# Timebase_shcematics.net
KiCad netlist of a schematic drawn in Altium Designer
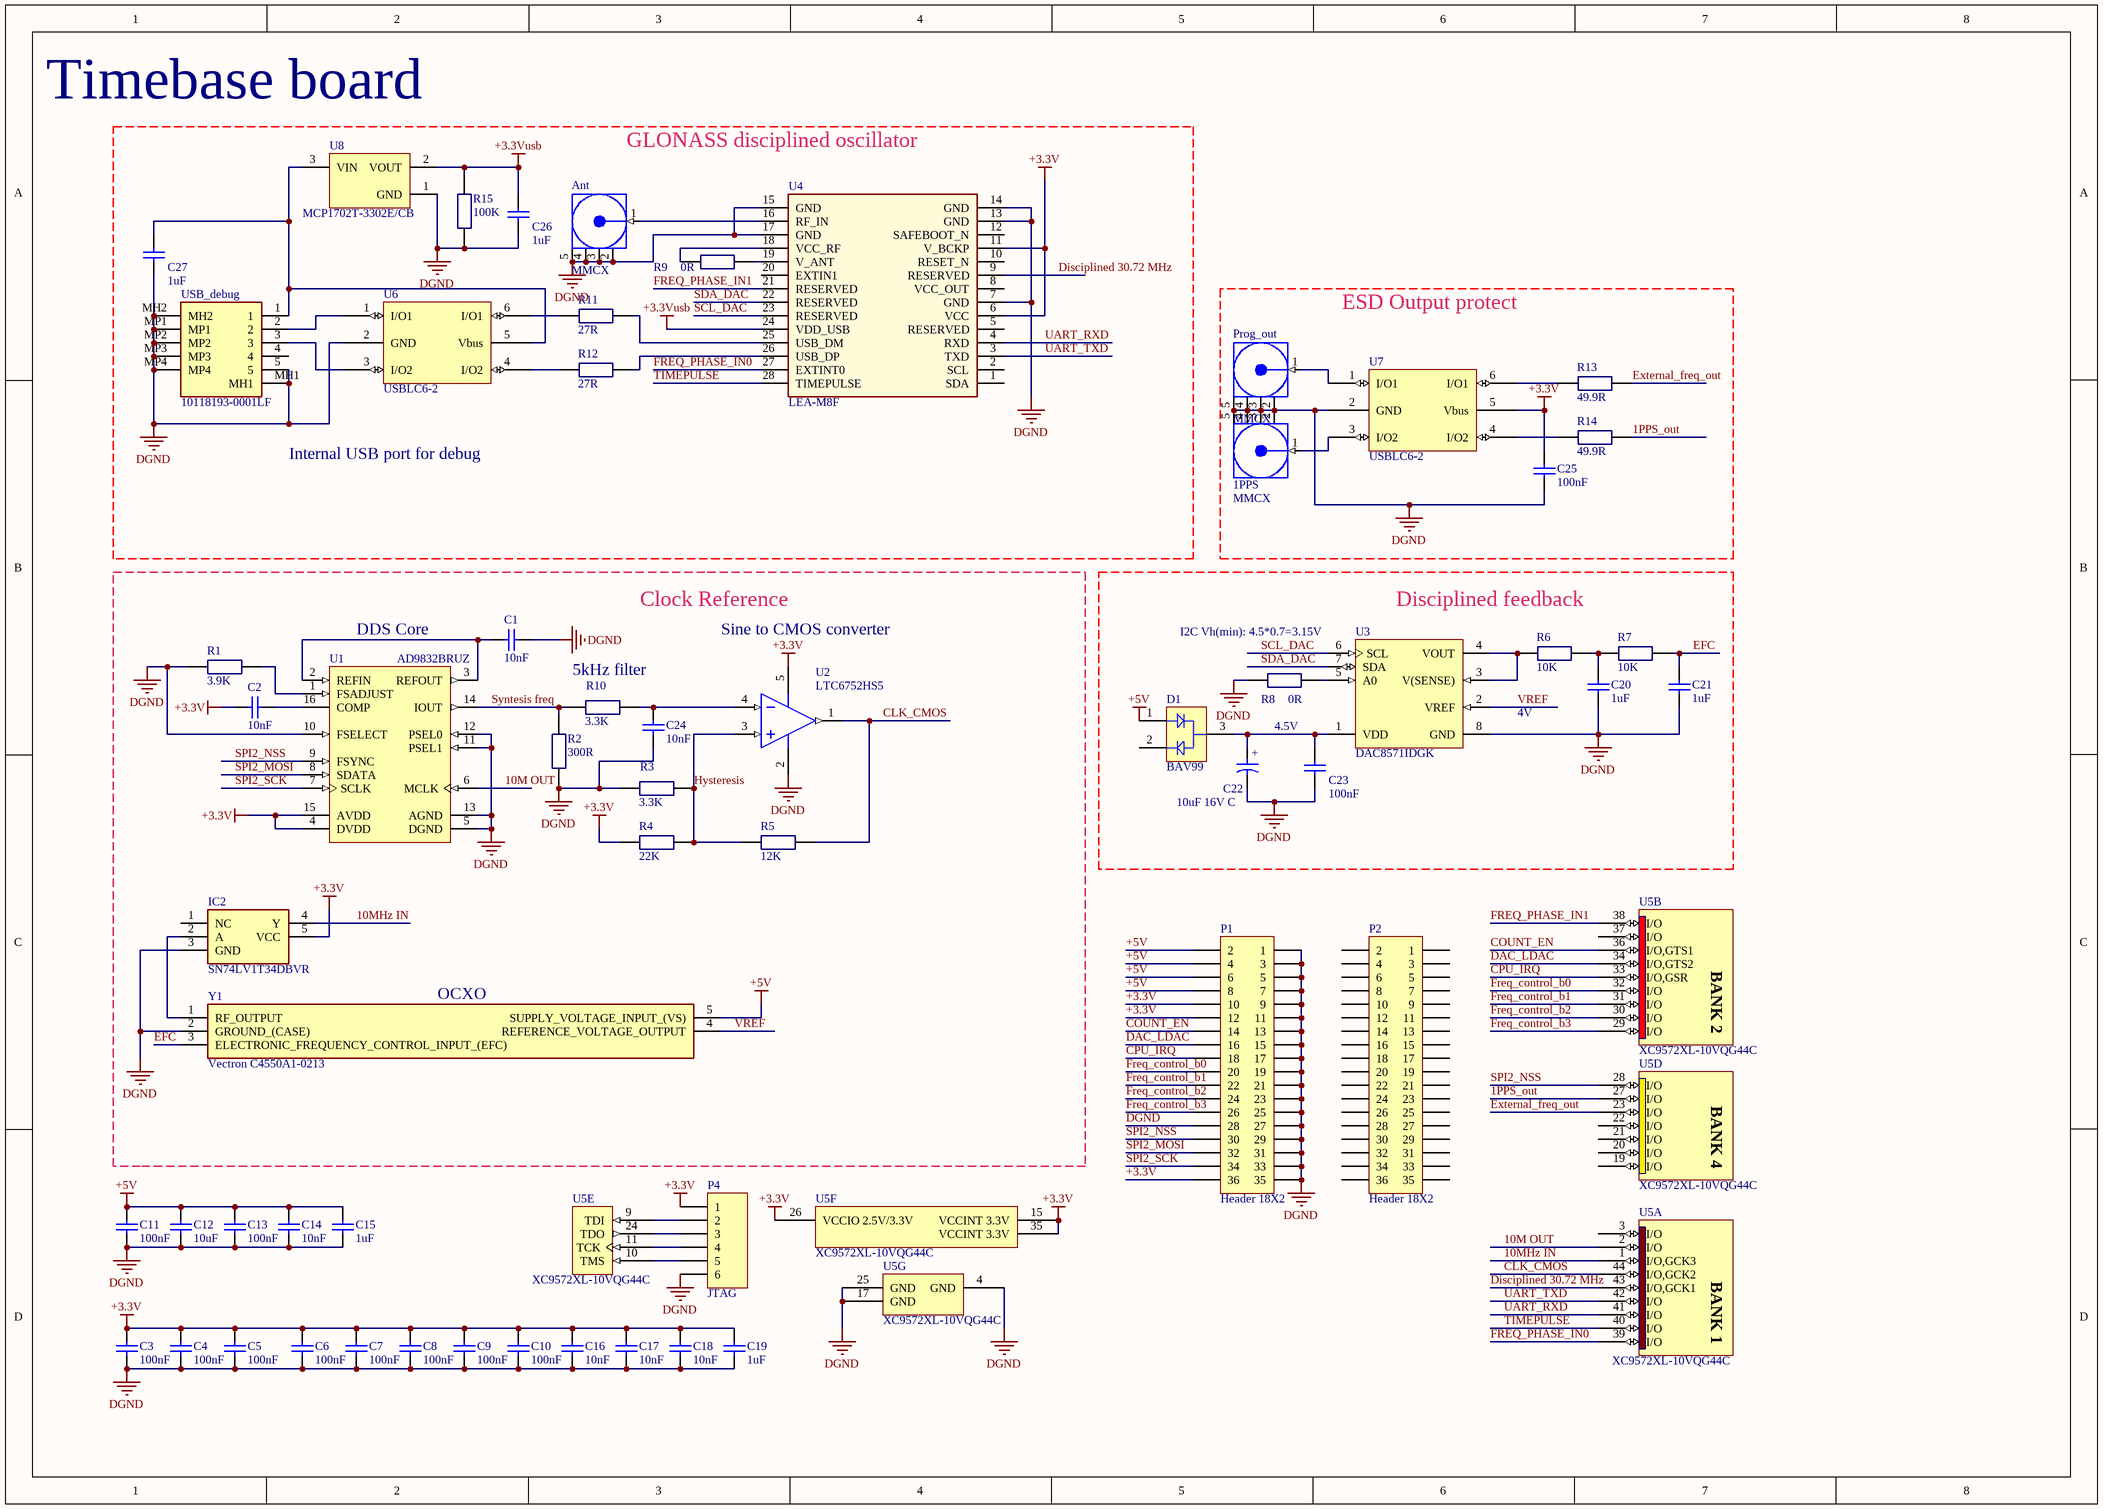
[diagram p0: Timebase_shcematics.SchDoc]

(export (version "E")
  (design (tool "Eeschema 10.0.6"))
  (components
    (comp (ref "1PPS")
      (value "MMCX")
      (footprint "MMCX2.54-V5")
      (description "RF Coaxial PCB Connector, MMCX; Thru-Hole, Vertical Mount Plug,  50 Ohm Impedance")
      (fields (field (name "PUBLISHER") "Altium Limited"))
      (libsource (lib "Miscellaneous Connectors") (part "COAX-M"))
    )
    (comp (ref "Ant")
      (value "MMCX")
      (footprint "MMCX2.54-V5")
      (description "RF Coaxial PCB Connector, MMCX; Thru-Hole, Vertical Mount Plug,  50 Ohm Impedance")
      (fields (field (name "PUBLISHER") "Altium Limited"))
      (libsource (lib "Miscellaneous Connectors") (part "COAX-M"))
    )
    (comp (ref "C1")
      (value "10nF")
      (footprint "CAP 0603")
      (description "Capacitor (Semiconductor SIM Model)")
      (fields (field (name "PUBLISHER") "Altium Limited"))
      (libsource (lib "Miscellaneous Devices") (part "Cap Semi"))
    )
    (comp (ref "C2")
      (value "10nF")
      (footprint "CAP 0603")
      (description "Capacitor (Semiconductor SIM Model)")
      (fields (field (name "PUBLISHER") "Altium Limited"))
      (libsource (lib "Miscellaneous Devices") (part "Cap Semi"))
    )
    (comp (ref "C3")
      (value "100nF")
      (footprint "CAP 0603")
      (description "Capacitor (Semiconductor SIM Model)")
      (fields (field (name "PUBLISHER") "Altium Limited"))
      (libsource (lib "Miscellaneous Devices") (part "Cap Semi"))
    )
    (comp (ref "C4")
      (value "100nF")
      (footprint "CAP 0603")
      (description "Capacitor (Semiconductor SIM Model)")
      (fields (field (name "PUBLISHER") "Altium Limited"))
      (libsource (lib "Miscellaneous Devices") (part "Cap Semi"))
    )
    (comp (ref "C5")
      (value "100nF")
      (footprint "CAP 0603")
      (description "Capacitor (Semiconductor SIM Model)")
      (fields (field (name "PUBLISHER") "Altium Limited"))
      (libsource (lib "Miscellaneous Devices") (part "Cap Semi"))
    )
    (comp (ref "C6")
      (value "100nF")
      (footprint "CAP 0603")
      (description "Capacitor (Semiconductor SIM Model)")
      (fields (field (name "PUBLISHER") "Altium Limited"))
      (libsource (lib "Miscellaneous Devices") (part "Cap Semi"))
    )
    (comp (ref "C7")
      (value "100nF")
      (footprint "CAP 0603")
      (description "Capacitor (Semiconductor SIM Model)")
      (fields (field (name "PUBLISHER") "Altium Limited"))
      (libsource (lib "Miscellaneous Devices") (part "Cap Semi"))
    )
    (comp (ref "C8")
      (value "100nF")
      (footprint "CAP 0603")
      (description "Capacitor (Semiconductor SIM Model)")
      (fields (field (name "PUBLISHER") "Altium Limited"))
      (libsource (lib "Miscellaneous Devices") (part "Cap Semi"))
    )
    (comp (ref "C9")
      (value "100nF")
      (footprint "CAP 0603")
      (description "Capacitor (Semiconductor SIM Model)")
      (fields (field (name "PUBLISHER") "Altium Limited"))
      (libsource (lib "Miscellaneous Devices") (part "Cap Semi"))
    )
    (comp (ref "C10")
      (value "100nF")
      (footprint "CAP 0603")
      (description "Capacitor (Semiconductor SIM Model)")
      (fields (field (name "PUBLISHER") "Altium Limited"))
      (libsource (lib "Miscellaneous Devices") (part "Cap Semi"))
    )
    (comp (ref "C11")
      (value "100nF")
      (footprint "CAP 0603")
      (description "Capacitor (Semiconductor SIM Model)")
      (fields (field (name "PUBLISHER") "Altium Limited"))
      (libsource (lib "Miscellaneous Devices") (part "Cap Semi"))
    )
    (comp (ref "C12")
      (value "10uF")
      (footprint "CAP 0603")
      (description "Capacitor (Semiconductor SIM Model)")
      (fields (field (name "PUBLISHER") "Altium Limited"))
      (libsource (lib "Miscellaneous Devices") (part "Cap Semi"))
    )
    (comp (ref "C13")
      (value "100nF")
      (footprint "CAP 0603")
      (description "Capacitor (Semiconductor SIM Model)")
      (fields (field (name "PUBLISHER") "Altium Limited"))
      (libsource (lib "Miscellaneous Devices") (part "Cap Semi"))
    )
    (comp (ref "C14")
      (value "10nF")
      (footprint "CAP 0603")
      (description "Capacitor (Semiconductor SIM Model)")
      (fields (field (name "PUBLISHER") "Altium Limited"))
      (libsource (lib "Miscellaneous Devices") (part "Cap Semi"))
    )
    (comp (ref "C15")
      (value "1uF")
      (footprint "CAP 0603")
      (description "Capacitor (Semiconductor SIM Model)")
      (fields (field (name "PUBLISHER") "Altium Limited"))
      (libsource (lib "Miscellaneous Devices") (part "Cap Semi"))
    )
    (comp (ref "C16")
      (value "10nF")
      (footprint "CAP 0603")
      (description "Capacitor (Semiconductor SIM Model)")
      (fields (field (name "PUBLISHER") "Altium Limited"))
      (libsource (lib "Miscellaneous Devices") (part "Cap Semi"))
    )
    (comp (ref "C17")
      (value "10nF")
      (footprint "CAP 0603")
      (description "Capacitor (Semiconductor SIM Model)")
      (fields (field (name "PUBLISHER") "Altium Limited"))
      (libsource (lib "Miscellaneous Devices") (part "Cap Semi"))
    )
    (comp (ref "C18")
      (value "10nF")
      (footprint "CAP 0603")
      (description "Capacitor (Semiconductor SIM Model)")
      (fields (field (name "PUBLISHER") "Altium Limited"))
      (libsource (lib "Miscellaneous Devices") (part "Cap Semi"))
    )
    (comp (ref "C19")
      (value "1uF")
      (footprint "CAP 0603")
      (description "Capacitor (Semiconductor SIM Model)")
      (fields (field (name "PUBLISHER") "Altium Limited"))
      (libsource (lib "Miscellaneous Devices") (part "Cap Semi"))
    )
    (comp (ref "C20")
      (value "1uF")
      (footprint "CAP 0603")
      (description "Capacitor (Semiconductor SIM Model)")
      (fields (field (name "PUBLISHER") "Altium Limited"))
      (libsource (lib "Miscellaneous Devices") (part "Cap Semi"))
    )
    (comp (ref "C21")
      (value "1uF")
      (footprint "CAP 0603")
      (description "Capacitor (Semiconductor SIM Model)")
      (fields (field (name "PUBLISHER") "Altium Limited"))
      (libsource (lib "Miscellaneous Devices") (part "Cap Semi"))
    )
    (comp (ref "C22")
      (value "10uF 16V C")
      (footprint "CAPMP6032X280N")
      (description "Polarised capacitor")
      (fields
        (field (name "PART NUMBER") "CTE6032-28_10UF_25V_10%_LESR0500")
        (field (name "VOLTAGE") "25V")
        (field (name "AUTHOR") "CERN DEM JLC")
      )
      (libsource (lib "Capacitors") (part "Capacitor - polarized"))
    )
    (comp (ref "C23")
      (value "100nF")
      (footprint "CAP 0603")
      (description "Capacitor (Semiconductor SIM Model)")
      (fields (field (name "PUBLISHER") "Altium Limited"))
      (libsource (lib "Miscellaneous Devices") (part "Cap Semi"))
    )
    (comp (ref "C24")
      (value "10nF")
      (footprint "CAP 0603")
      (description "Capacitor (Semiconductor SIM Model)")
      (fields (field (name "PUBLISHER") "Altium Limited"))
      (libsource (lib "Miscellaneous Devices") (part "Cap Semi"))
    )
    (comp (ref "C25")
      (value "100nF")
      (footprint "CAP 0603")
      (description "Capacitor (Semiconductor SIM Model)")
      (fields (field (name "PUBLISHER") "Altium Limited"))
      (libsource (lib "Miscellaneous Devices") (part "Cap Semi"))
    )
    (comp (ref "C26")
      (value "1uF")
      (footprint "CAP 0603")
      (description "Capacitor (Semiconductor SIM Model)")
      (fields (field (name "PUBLISHER") "Altium Limited"))
      (libsource (lib "Miscellaneous Devices") (part "Cap Semi"))
    )
    (comp (ref "C27")
      (value "1uF")
      (footprint "CAP 0603")
      (description "Capacitor (Semiconductor SIM Model)")
      (fields (field (name "PUBLISHER") "Altium Limited"))
      (libsource (lib "Miscellaneous Devices") (part "Cap Semi"))
    )
    (comp (ref "D1")
      (value "BAV99")
      (footprint "INF-SOT23_N")
      (description "Silicon Switching Diode, SOT23, Reel, Green")
      (fields (field (name "MANUFACTURER") "Infineon"))
      (libsource (lib "Infineon_Transistor_&_Diode") (part "BAV99"))
    )
    (comp (ref "IC2")
      (value "SN74LV1T34DBVR")
      (footprint "SamacSys:SOT95P280X145-5N")
      (description "Integrated Circuit")
      (fields (field (name "MOUSER PART NUMBER") "595-SN74LV1T34DBVR"))
      (libsource (lib "*") (part "SN74LV1T34DBVR"))
    )
    (comp (ref "P1")
      (value "Header 18X2")
      (footprint "HDR2X18")
      (description "Header, 18-Pin, Dual row")
      (fields (field (name "PUBLISHER") "Altium Limited"))
      (libsource (lib "Miscellaneous Connectors") (part "Header 18X2"))
    )
    (comp (ref "P2")
      (value "Header 18X2")
      (footprint "HDR2X18")
      (description "Header, 18-Pin, Dual row")
      (fields (field (name "PUBLISHER") "Altium Limited"))
      (libsource (lib "Miscellaneous Connectors") (part "Header 18X2"))
    )
    (comp (ref "P4")
      (value "JTAG")
      (footprint "HDR1X6")
      (description "Header, 6-Pin")
      (fields (field (name "PUBLISHER") "Altium Limited"))
      (libsource (lib "Miscellaneous Connectors") (part "Header 6"))
    )
    (comp (ref "Prog_out")
      (value "MMCX")
      (footprint "MMCX2.54-V5")
      (description "RF Coaxial PCB Connector, MMCX; Thru-Hole, Vertical Mount Plug,  50 Ohm Impedance")
      (fields (field (name "PUBLISHER") "Altium Limited"))
      (libsource (lib "Miscellaneous Connectors") (part "COAX-M"))
    )
    (comp (ref "R1")
      (value "3.9K")
      (footprint "1608[0603]")
      (libsource (lib "Микрон-3") (part "Resistor 0805"))
    )
    (comp (ref "R2")
      (value "300R")
      (footprint "Yegeo 0603")
      (libsource (lib "Микрон-3") (part "Resistor 0805"))
    )
    (comp (ref "R3")
      (value "3.3K")
      (footprint "Yegeo 0603")
      (libsource (lib "Микрон-3") (part "Resistor 0805"))
    )
    (comp (ref "R4")
      (value "22K")
      (footprint "Yegeo 0603")
      (libsource (lib "Микрон-3") (part "Resistor 0805"))
    )
    (comp (ref "R5")
      (value "12K")
      (footprint "Yegeo 0603")
      (libsource (lib "Микрон-3") (part "Resistor 0805"))
    )
    (comp (ref "R6")
      (value "10K")
      (footprint "1608[0603]")
      (libsource (lib "Микрон-3") (part "Resistor 0805"))
    )
    (comp (ref "R7")
      (value "10K")
      (footprint "1608[0603]")
      (libsource (lib "Микрон-3") (part "Resistor 0805"))
    )
    (comp (ref "R8")
      (value "0R")
      (footprint "1608[0603]")
      (libsource (lib "Микрон-3") (part "Resistor 0805"))
    )
    (comp (ref "R9")
      (value "0R")
      (footprint "1608[0603]")
      (libsource (lib "Микрон-3") (part "Resistor 0805"))
    )
    (comp (ref "R10")
      (value "3.3K")
      (footprint "Yegeo 0603")
      (libsource (lib "Микрон-3") (part "Resistor 0805"))
    )
    (comp (ref "R11")
      (value "27R")
      (footprint "1608[0603]")
      (libsource (lib "Микрон-3") (part "Resistor 0805"))
    )
    (comp (ref "R12")
      (value "27R")
      (footprint "1608[0603]")
      (libsource (lib "Микрон-3") (part "Resistor 0805"))
    )
    (comp (ref "R13")
      (value "49.9R")
      (footprint "1608[0603]")
      (libsource (lib "Микрон-3") (part "Resistor 0805"))
    )
    (comp (ref "R14")
      (value "49.9R")
      (footprint "1608[0603]")
      (libsource (lib "Микрон-3") (part "Resistor 0805"))
    )
    (comp (ref "R15")
      (value "100K")
      (footprint "1608[0603]")
      (libsource (lib "Микрон-3") (part "Resistor 0805"))
    )
    (comp (ref "U1")
      (value "AD9832BRUZ")
      (footprint "ADI-RU-16_N")
      (description "25 MHz Direct Digital Synthesizer, Waveform Generator, 10-Bit, Serial, RU-16, 96 Tube, Pb-Free")
      (libsource (lib "Ramp-generator") (part "AD9832BRUZ"))
    )
    (comp (ref "U2")
      (value "LTC6752HS5")
      (footprint "TI-DBV5_N")
      (fields (field (name "MANUFACTURER") "Texas Instruments") (field (name "PARTNUMBER") "OPA353NA/250"))
      (libsource (lib "TI Amplifiers and Linear Operational Amplifier Precision Amplifier Part One") (part "OPA353NA/250"))
    )
    (comp (ref "U3")
      (value "DAC8571IDGK")
      (footprint "TI-DGK8_N")
      (fields (field (name "MANUFACTURER") "Texas Instruments"))
      (libsource (lib "TI Data Converters Digital to Analog Converter") (part "DAC8571IDGK"))
    )
    (comp (ref "U4")
      (value "LEA-M8F")
      (footprint "LEA")
      (description "u-blox LEA GNSS module")
      (fields (field (name "MANUFACTURER") "u-blox"))
      (libsource (lib "ubloxLib") (part "LEA"))
    )
    (comp (ref "U5")
      (value "XC9572XL-10VQG44C")
      (footprint "VQG44_N")
      (fields (field (name "PUBLISHER") "Altium Limited"))
      (libsource (lib "") (part "XC9572XL-10VQG44C_1"))
    )
    (comp (ref "U6") (value "USBLC6-2") (footprint "SOT23-6L") (libsource (lib "Микрон-3") (part "USBLC6-2")))
    (comp (ref "U7") (value "USBLC6-2") (footprint "SOT23-6L") (libsource (lib "Микрон-3") (part "USBLC6-2")))
    (comp (ref "U8")
      (value "MCP1702T-3302E/CB")
      (footprint "SOT-23A-CB3_N")
      (description "250 mA Low Quiescent Current LDO Regulator, 3-Pin SOT-23A, Extended Temperature, Tape and Reel")
      (fields (field (name "PUBLISHER") "Altium Limited"))
      (libsource (lib "Microchip Power Mgt Line Regulator") (part "MCP1702T-3302E/CB"))
    )
    (comp (ref "USB_debug")
      (value "10118193-0001LF")
      (footprint "SamacSys:101181930001LF")
      (description "Connector")
      (fields (field (name "MOUSER PART NUMBER") "649-10118193-0001LF"))
      (libsource (lib "*") (part "10118193-0001LF"))
    )
    (comp (ref "Y1")
      (value "Vectron C4550A1-0213")
      (footprint "SamacSys:C4550C508SV120RFSA11128MHZ")
      (description "Crystal or Oscillator")
      (libsource (lib "SamacSys") (part "C4550C508SV120RFSA1112.8MHZ"))
    )
  )
  (nets
    (net (code "1") (name "+3.3V") (class "Default")
      (node (ref "C10") (pin "2") (pinfunction "2_2") (pintype "passive"))
      (node (ref "C16") (pin "2") (pinfunction "2_2") (pintype "passive"))
      (node (ref "C17") (pin "2") (pinfunction "2_2") (pintype "passive"))
      (node (ref "C18") (pin "2") (pinfunction "2_2") (pintype "passive"))
      (node (ref "C19") (pin "2") (pinfunction "2_2") (pintype "passive"))
      (node (ref "C2") (pin "1") (pinfunction "1_1") (pintype "passive"))
      (node (ref "C25") (pin "2") (pinfunction "2_2") (pintype "passive"))
      (node (ref "C3") (pin "2") (pinfunction "2_2") (pintype "passive"))
      (node (ref "C4") (pin "2") (pinfunction "2_2") (pintype "passive"))
      (node (ref "C5") (pin "2") (pinfunction "2_2") (pintype "passive"))
      (node (ref "C6") (pin "2") (pinfunction "2_2") (pintype "passive"))
      (node (ref "C7") (pin "2") (pinfunction "2_2") (pintype "passive"))
      (node (ref "C8") (pin "2") (pinfunction "2_2") (pintype "passive"))
      (node (ref "C9") (pin "2") (pinfunction "2_2") (pintype "passive"))
      (node (ref "IC2") (pin "5") (pinfunction "VCC_5") (pintype "passive"))
      (node (ref "P1") (pin "10") (pinfunction "10_10") (pintype "passive"))
      (node (ref "P1") (pin "12") (pinfunction "12_12") (pintype "passive"))
      (node (ref "P1") (pin "36") (pinfunction "36_36") (pintype "passive"))
      (node (ref "P4") (pin "1") (pinfunction "1_1") (pintype "passive"))
      (node (ref "R4") (pin "2") (pinfunction "2_2") (pintype "passive"))
      (node (ref "U1") (pin "15") (pinfunction "AVDD_15") (pintype "power_in"))
      (node (ref "U1") (pin "4") (pinfunction "DVDD_4") (pintype "power_in"))
      (node (ref "U2") (pin "5") (pinfunction "V+_5") (pintype "power_in"))
      (node (ref "U4") (pin "11") (pinfunction "V_BCKP_11") (pintype "passive"))
      (node (ref "U4") (pin "6") (pinfunction "VCC_6") (pintype "passive"))
      (node (ref "U5") (pin "15") (pinfunction "VCCINT_3.3V_15") (pintype "power_in"))
      (node (ref "U5") (pin "26") (pinfunction "VCCIO_2.5V/3.3V_26") (pintype "power_in"))
      (node (ref "U5") (pin "35") (pinfunction "VCCINT_3.3V_35") (pintype "power_in"))
      (node (ref "U7") (pin "5") (pinfunction "Vbus_5") (pintype "power_in"))
    )
    (net (code "2") (name "+3.3Vusb") (class "Default")
      (node (ref "C26") (pin "2") (pinfunction "2_2") (pintype "passive"))
      (node (ref "R15") (pin "1") (pinfunction "A_1") (pintype "passive"))
      (node (ref "U4") (pin "24") (pinfunction "VDD_USB_24") (pintype "passive"))
      (node (ref "U8") (pin "2") (pinfunction "VOUT_2") (pintype "power_in"))
    )
    (net (code "3") (name "+5V") (class "Default")
      (node (ref "C11") (pin "2") (pinfunction "2_2") (pintype "passive"))
      (node (ref "C12") (pin "2") (pinfunction "2_2") (pintype "passive"))
      (node (ref "C13") (pin "2") (pinfunction "2_2") (pintype "passive"))
      (node (ref "C14") (pin "2") (pinfunction "2_2") (pintype "passive"))
      (node (ref "C15") (pin "2") (pinfunction "2_2") (pintype "passive"))
      (node (ref "D1") (pin "1") (pinfunction "A1_1") (pintype "passive"))
      (node (ref "P1") (pin "2") (pinfunction "2_2") (pintype "passive"))
      (node (ref "P1") (pin "4") (pinfunction "4_4") (pintype "passive"))
      (node (ref "P1") (pin "6") (pinfunction "6_6") (pintype "passive"))
      (node (ref "P1") (pin "8") (pinfunction "8_8") (pintype "passive"))
      (node (ref "Y1") (pin "5") (pinfunction "SUPPLY_VOLTAGE_INPUT_(VS)_5") (pintype "passive"))
    )
    (net (code "4") (name "/1PPS_out") (class "Default")
      (node (ref "R14") (pin "1") (pinfunction "A_1") (pintype "passive"))
      (node (ref "U5") (pin "27") (pinfunction "I/O_27") (pintype "bidirectional"))
    )
    (net (code "5") (name "/10M OUT") (class "Default")
      (node (ref "U1") (pin "6") (pinfunction "MCLK_6") (pintype "input"))
      (node (ref "U5") (pin "2") (pinfunction "I/O_2") (pintype "bidirectional"))
    )
    (net (code "6") (name "/10MHz IN") (class "Default")
      (node (ref "IC2") (pin "4") (pinfunction "Y_4") (pintype "passive"))
      (node (ref "U5") (pin "1") (pinfunction "I/O,GCK3_1") (pintype "bidirectional"))
    )
    (net (code "7") (name "/CLK_CMOS") (class "Default")
      (node (ref "R5") (pin "1") (pinfunction "A_1") (pintype "passive"))
      (node (ref "U2") (pin "1") (pinfunction "OUT_1") (pintype "output"))
      (node (ref "U5") (pin "44") (pinfunction "I/O,GCK2_44") (pintype "bidirectional"))
    )
    (net (code "8") (name "/COUNT_EN") (class "Default")
      (node (ref "P1") (pin "14") (pinfunction "14_14") (pintype "passive"))
      (node (ref "U5") (pin "36") (pinfunction "I/O,GTS1_36") (pintype "bidirectional"))
    )
    (net (code "9") (name "/CPU_IRQ") (class "Default")
      (node (ref "P1") (pin "18") (pinfunction "18_18") (pintype "passive"))
      (node (ref "U5") (pin "33") (pinfunction "I/O,GSR_33") (pintype "bidirectional"))
    )
    (net (code "10") (name "/DAC_LDAC") (class "Default")
      (node (ref "P1") (pin "16") (pinfunction "16_16") (pintype "passive"))
      (node (ref "U5") (pin "34") (pinfunction "I/O,GTS2_34") (pintype "bidirectional"))
    )
    (net (code "11") (name "/Disciplined 30.72 MHz") (class "Default")
      (node (ref "U4") (pin "9") (pinfunction "RESERVED_9") (pintype "passive"))
      (node (ref "U5") (pin "43") (pinfunction "I/O,GCK1_43") (pintype "bidirectional"))
    )
    (net (code "12") (name "/EFC") (class "Default")
      (node (ref "C21") (pin "2") (pinfunction "2_2") (pintype "passive"))
      (node (ref "R7") (pin "1") (pinfunction "A_1") (pintype "passive"))
      (node (ref "Y1") (pin "3") (pinfunction "ELECTRONIC_FREQUENCY_CONTROL_INPUT_(EFC)_3") (pintype "passive"))
    )
    (net (code "13") (name "/External_freq_out") (class "Default")
      (node (ref "R13") (pin "1") (pinfunction "A_1") (pintype "passive"))
      (node (ref "U5") (pin "23") (pinfunction "I/O_23") (pintype "bidirectional"))
    )
    (net (code "14") (name "/FREQ_PHASE_IN0") (class "Default")
      (node (ref "U4") (pin "27") (pinfunction "EXTINT0_27") (pintype "passive"))
      (node (ref "U5") (pin "39") (pinfunction "I/O_39") (pintype "bidirectional"))
    )
    (net (code "15") (name "/FREQ_PHASE_IN1") (class "Default")
      (node (ref "U4") (pin "21") (pinfunction "RESERVED_21") (pintype "passive"))
      (node (ref "U5") (pin "38") (pinfunction "I/O_38") (pintype "bidirectional"))
    )
    (net (code "16") (name "/Freq_control_b0") (class "Default")
      (node (ref "P1") (pin "20") (pinfunction "20_20") (pintype "passive"))
      (node (ref "U5") (pin "32") (pinfunction "I/O_32") (pintype "bidirectional"))
    )
    (net (code "17") (name "/Freq_control_b1") (class "Default")
      (node (ref "P1") (pin "22") (pinfunction "22_22") (pintype "passive"))
      (node (ref "U5") (pin "31") (pinfunction "I/O_31") (pintype "bidirectional"))
    )
    (net (code "18") (name "/Freq_control_b2") (class "Default")
      (node (ref "P1") (pin "24") (pinfunction "24_24") (pintype "passive"))
      (node (ref "U5") (pin "30") (pinfunction "I/O_30") (pintype "bidirectional"))
    )
    (net (code "19") (name "/Freq_control_b3") (class "Default")
      (node (ref "P1") (pin "26") (pinfunction "26_26") (pintype "passive"))
      (node (ref "U5") (pin "29") (pinfunction "I/O_29") (pintype "bidirectional"))
    )
    (net (code "20") (name "/Hysteresis") (class "Default")
      (node (ref "R3") (pin "1") (pinfunction "A_1") (pintype "passive"))
      (node (ref "R4") (pin "1") (pinfunction "A_1") (pintype "passive"))
      (node (ref "R5") (pin "2") (pinfunction "2_2") (pintype "passive"))
      (node (ref "U2") (pin "3") (pinfunction "IN+_3") (pintype "input"))
    )
    (net (code "21") (name "/SCL_DAC") (class "Default")
      (node (ref "U3") (pin "6") (pinfunction "SCL_6") (pintype "input"))
      (node (ref "U4") (pin "23") (pinfunction "RESERVED_23") (pintype "passive"))
    )
    (net (code "22") (name "/SDA_DAC") (class "Default")
      (node (ref "U3") (pin "7") (pinfunction "SDA_7") (pintype "bidirectional"))
      (node (ref "U4") (pin "22") (pinfunction "RESERVED_22") (pintype "passive"))
    )
    (net (code "23") (name "/SPI2_MOSI") (class "Default")
      (node (ref "P1") (pin "32") (pinfunction "32_32") (pintype "passive"))
      (node (ref "U1") (pin "8") (pinfunction "SDATA_8") (pintype "input"))
    )
    (net (code "24") (name "/SPI2_NSS") (class "Default")
      (node (ref "P1") (pin "30") (pinfunction "30_30") (pintype "passive"))
      (node (ref "U1") (pin "9") (pinfunction "FSYNC_9") (pintype "input"))
      (node (ref "U5") (pin "28") (pinfunction "I/O_28") (pintype "bidirectional"))
    )
    (net (code "25") (name "/SPI2_SCK") (class "Default")
      (node (ref "P1") (pin "34") (pinfunction "34_34") (pintype "passive"))
      (node (ref "U1") (pin "7") (pinfunction "SCLK_7") (pintype "input"))
    )
    (net (code "26") (name "/Syntesis freq") (class "Default")
      (node (ref "R10") (pin "2") (pinfunction "2_2") (pintype "passive"))
      (node (ref "R2") (pin "2") (pinfunction "2_2") (pintype "passive"))
      (node (ref "U1") (pin "14") (pinfunction "IOUT_14") (pintype "output"))
    )
    (net (code "27") (name "/TIMEPULSE") (class "Default")
      (node (ref "U4") (pin "28") (pinfunction "TIMEPULSE_28") (pintype "passive"))
      (node (ref "U5") (pin "40") (pinfunction "I/O_40") (pintype "bidirectional"))
    )
    (net (code "28") (name "/UART_RXD") (class "Default")
      (node (ref "U4") (pin "4") (pinfunction "RXD_4") (pintype "passive"))
      (node (ref "U5") (pin "41") (pinfunction "I/O_41") (pintype "bidirectional"))
    )
    (net (code "29") (name "/UART_TXD") (class "Default")
      (node (ref "U4") (pin "3") (pinfunction "TXD_3") (pintype "passive"))
      (node (ref "U5") (pin "42") (pinfunction "I/O_42") (pintype "bidirectional"))
    )
    (net (code "30") (name "/VREF") (class "Default")
      (node (ref "U3") (pin "2") (pinfunction "VREF_2") (pintype "input"))
      (node (ref "Y1") (pin "4") (pinfunction "REFERENCE_VOLTAGE_OUTPUT_4") (pintype "passive"))
    )
    (net (code "31") (name "DGND") (class "Default")
      (node (ref "1PPS") (pin "2") (pinfunction "GND_2") (pintype "power_in"))
      (node (ref "1PPS") (pin "3") (pinfunction "GND_3") (pintype "power_in"))
      (node (ref "1PPS") (pin "4") (pinfunction "GND_4") (pintype "power_in"))
      (node (ref "1PPS") (pin "5") (pinfunction "GND_5") (pintype "power_in"))
      (node (ref "Ant") (pin "2") (pinfunction "GND_2") (pintype "power_in"))
      (node (ref "Ant") (pin "3") (pinfunction "GND_3") (pintype "power_in"))
      (node (ref "Ant") (pin "4") (pinfunction "GND_4") (pintype "power_in"))
      (node (ref "Ant") (pin "5") (pinfunction "GND_5") (pintype "power_in"))
      (node (ref "C1") (pin "2") (pinfunction "2_2") (pintype "passive"))
      (node (ref "C10") (pin "1") (pinfunction "1_1") (pintype "passive"))
      (node (ref "C11") (pin "1") (pinfunction "1_1") (pintype "passive"))
      (node (ref "C12") (pin "1") (pinfunction "1_1") (pintype "passive"))
      (node (ref "C13") (pin "1") (pinfunction "1_1") (pintype "passive"))
      (node (ref "C14") (pin "1") (pinfunction "1_1") (pintype "passive"))
      (node (ref "C15") (pin "1") (pinfunction "1_1") (pintype "passive"))
      (node (ref "C16") (pin "1") (pinfunction "1_1") (pintype "passive"))
      (node (ref "C17") (pin "1") (pinfunction "1_1") (pintype "passive"))
      (node (ref "C18") (pin "1") (pinfunction "1_1") (pintype "passive"))
      (node (ref "C19") (pin "1") (pinfunction "1_1") (pintype "passive"))
      (node (ref "C20") (pin "1") (pinfunction "1_1") (pintype "passive"))
      (node (ref "C21") (pin "1") (pinfunction "1_1") (pintype "passive"))
      (node (ref "C22") (pin "2") (pinfunction "2_2") (pintype "passive"))
      (node (ref "C23") (pin "1") (pinfunction "1_1") (pintype "passive"))
      (node (ref "C24") (pin "1") (pinfunction "1_1") (pintype "passive"))
      (node (ref "C25") (pin "1") (pinfunction "1_1") (pintype "passive"))
      (node (ref "C26") (pin "1") (pinfunction "1_1") (pintype "passive"))
      (node (ref "C27") (pin "1") (pinfunction "1_1") (pintype "passive"))
      (node (ref "C3") (pin "1") (pinfunction "1_1") (pintype "passive"))
      (node (ref "C4") (pin "1") (pinfunction "1_1") (pintype "passive"))
      (node (ref "C5") (pin "1") (pinfunction "1_1") (pintype "passive"))
      (node (ref "C6") (pin "1") (pinfunction "1_1") (pintype "passive"))
      (node (ref "C7") (pin "1") (pinfunction "1_1") (pintype "passive"))
      (node (ref "C8") (pin "1") (pinfunction "1_1") (pintype "passive"))
      (node (ref "C9") (pin "1") (pinfunction "1_1") (pintype "passive"))
      (node (ref "IC2") (pin "3") (pinfunction "GND_3") (pintype "passive"))
      (node (ref "P1") (pin "1") (pinfunction "1_1") (pintype "passive"))
      (node (ref "P1") (pin "11") (pinfunction "11_11") (pintype "passive"))
      (node (ref "P1") (pin "13") (pinfunction "13_13") (pintype "passive"))
      (node (ref "P1") (pin "15") (pinfunction "15_15") (pintype "passive"))
      (node (ref "P1") (pin "17") (pinfunction "17_17") (pintype "passive"))
      (node (ref "P1") (pin "19") (pinfunction "19_19") (pintype "passive"))
      (node (ref "P1") (pin "21") (pinfunction "21_21") (pintype "passive"))
      (node (ref "P1") (pin "23") (pinfunction "23_23") (pintype "passive"))
      (node (ref "P1") (pin "25") (pinfunction "25_25") (pintype "passive"))
      (node (ref "P1") (pin "27") (pinfunction "27_27") (pintype "passive"))
      (node (ref "P1") (pin "28") (pinfunction "28_28") (pintype "passive"))
      (node (ref "P1") (pin "29") (pinfunction "29_29") (pintype "passive"))
      (node (ref "P1") (pin "3") (pinfunction "3_3") (pintype "passive"))
      (node (ref "P1") (pin "31") (pinfunction "31_31") (pintype "passive"))
      (node (ref "P1") (pin "33") (pinfunction "33_33") (pintype "passive"))
      (node (ref "P1") (pin "35") (pinfunction "35_35") (pintype "passive"))
      (node (ref "P1") (pin "5") (pinfunction "5_5") (pintype "passive"))
      (node (ref "P1") (pin "7") (pinfunction "7_7") (pintype "passive"))
      (node (ref "P1") (pin "9") (pinfunction "9_9") (pintype "passive"))
      (node (ref "P4") (pin "6") (pinfunction "6_6") (pintype "passive"))
      (node (ref "Prog_out") (pin "2") (pinfunction "GND_2") (pintype "power_in"))
      (node (ref "Prog_out") (pin "3") (pinfunction "GND_3") (pintype "power_in"))
      (node (ref "Prog_out") (pin "4") (pinfunction "GND_4") (pintype "power_in"))
      (node (ref "Prog_out") (pin "5") (pinfunction "GND_5") (pintype "power_in"))
      (node (ref "R1") (pin "2") (pinfunction "2_2") (pintype "passive"))
      (node (ref "R15") (pin "2") (pinfunction "2_2") (pintype "passive"))
      (node (ref "R2") (pin "1") (pinfunction "A_1") (pintype "passive"))
      (node (ref "R3") (pin "2") (pinfunction "2_2") (pintype "passive"))
      (node (ref "R8") (pin "2") (pinfunction "2_2") (pintype "passive"))
      (node (ref "U1") (pin "10") (pinfunction "FSELECT_10") (pintype "input"))
      (node (ref "U1") (pin "11") (pinfunction "PSEL1_11") (pintype "input"))
      (node (ref "U1") (pin "12") (pinfunction "PSEL0_12") (pintype "input"))
      (node (ref "U1") (pin "13") (pinfunction "AGND_13") (pintype "power_in"))
      (node (ref "U1") (pin "5") (pinfunction "DGND_5") (pintype "power_in"))
      (node (ref "U2") (pin "2") (pinfunction "V-_2") (pintype "power_in"))
      (node (ref "U3") (pin "8") (pinfunction "GND_8") (pintype "power_in"))
      (node (ref "U4") (pin "13") (pinfunction "GND_13") (pintype "passive"))
      (node (ref "U4") (pin "14") (pinfunction "GND_14") (pintype "passive"))
      (node (ref "U4") (pin "15") (pinfunction "GND_15") (pintype "passive"))
      (node (ref "U4") (pin "17") (pinfunction "GND_17") (pintype "passive"))
      (node (ref "U4") (pin "7") (pinfunction "GND_7") (pintype "passive"))
      (node (ref "U5") (pin "17") (pinfunction "GND_17") (pintype "power_in"))
      (node (ref "U5") (pin "25") (pinfunction "GND_25") (pintype "power_in"))
      (node (ref "U5") (pin "4") (pinfunction "GND_4") (pintype "power_in"))
      (node (ref "U6") (pin "2") (pinfunction "GND_2") (pintype "power_in"))
      (node (ref "U7") (pin "2") (pinfunction "GND_2") (pintype "power_in"))
      (node (ref "U8") (pin "1") (pinfunction "GND_1") (pintype "power_in"))
      (node (ref "USB_debug") (pin "5") (pinfunction "5_5") (pintype "passive"))
      (node (ref "USB_debug") (pin "MH1") (pinfunction "MH1_MH1") (pintype "passive"))
      (node (ref "USB_debug") (pin "MH2") (pinfunction "MH2_MH2") (pintype "passive"))
      (node (ref "USB_debug") (pin "MP1") (pinfunction "MP1_MP1") (pintype "passive"))
      (node (ref "USB_debug") (pin "MP2") (pinfunction "MP2_MP2") (pintype "passive"))
      (node (ref "USB_debug") (pin "MP3") (pinfunction "MP3_MP3") (pintype "passive"))
      (node (ref "USB_debug") (pin "MP4") (pinfunction "MP4_MP4") (pintype "passive"))
      (node (ref "Y1") (pin "2") (pinfunction "GROUND_(CASE)_2") (pintype "passive"))
    )
    (net (code "32") (name "Net-(1PPS-Signal)") (class "Default")
      (node (ref "1PPS") (pin "1") (pinfunction "Signal_1") (pintype "input"))
      (node (ref "U7") (pin "3") (pinfunction "I/O2_3") (pintype "bidirectional"))
    )
    (net (code "33") (name "Net-(Ant-Signal)") (class "Default")
      (node (ref "Ant") (pin "1") (pinfunction "Signal_1") (pintype "input"))
      (node (ref "U4") (pin "16") (pinfunction "RF_IN_16") (pintype "passive"))
    )
    (net (code "34") (name "Net-(D1-C)") (class "Default")
      (node (ref "C22") (pin "1") (pinfunction "1_1") (pintype "passive"))
      (node (ref "C23") (pin "2") (pinfunction "2_2") (pintype "passive"))
      (node (ref "D1") (pin "3") (pinfunction "C_3") (pintype "passive"))
      (node (ref "U3") (pin "1") (pinfunction "VDD_1") (pintype "power_in"))
    )
    (net (code "35") (name "Net-(IC2-A)") (class "Default")
      (node (ref "IC2") (pin "2") (pinfunction "A_2") (pintype "passive"))
      (node (ref "Y1") (pin "1") (pinfunction "RF_OUTPUT_1") (pintype "passive"))
    )
    (net (code "36") (name "Net-(Prog_out-Signal)") (class "Default")
      (node (ref "Prog_out") (pin "1") (pinfunction "Signal_1") (pintype "input"))
      (node (ref "U7") (pin "1") (pinfunction "I/O1_1") (pintype "bidirectional"))
    )
    (net (code "37") (name "Net-(R1-A)") (class "Default")
      (node (ref "R1") (pin "1") (pinfunction "A_1") (pintype "passive"))
      (node (ref "U1") (pin "1") (pinfunction "FSADJUST_1") (pintype "input"))
    )
    (net (code "38") (name "Net-(R6-A)") (class "Default")
      (node (ref "C20") (pin "2") (pinfunction "2_2") (pintype "passive"))
      (node (ref "R6") (pin "1") (pinfunction "A_1") (pintype "passive"))
      (node (ref "R7") (pin "2") (pinfunction "2_2") (pintype "passive"))
    )
    (net (code "39") (name "Net-(R8-A)") (class "Default")
      (node (ref "R8") (pin "1") (pinfunction "A_1") (pintype "passive"))
      (node (ref "U3") (pin "5") (pinfunction "A0_5") (pintype "input"))
    )
    (net (code "40") (name "Net-(R9-A)") (class "Default")
      (node (ref "R9") (pin "1") (pinfunction "A_1") (pintype "passive"))
      (node (ref "U4") (pin "19") (pinfunction "V_ANT_19") (pintype "passive"))
    )
    (net (code "41") (name "Net-(R10-A)") (class "Default")
      (node (ref "C24") (pin "2") (pinfunction "2_2") (pintype "passive"))
      (node (ref "R10") (pin "1") (pinfunction "A_1") (pintype "passive"))
      (node (ref "U2") (pin "4") (pinfunction "IN-_4") (pintype "input"))
    )
    (net (code "42") (name "Net-(R11-A)") (class "Default")
      (node (ref "R11") (pin "1") (pinfunction "A_1") (pintype "passive"))
      (node (ref "U4") (pin "25") (pinfunction "USB_DM_25") (pintype "passive"))
    )
    (net (code "43") (name "Net-(R11-Pad2)") (class "Default")
      (node (ref "R11") (pin "2") (pinfunction "2_2") (pintype "passive"))
      (node (ref "U6") (pin "6") (pinfunction "I/O1_6") (pintype "bidirectional"))
    )
    (net (code "44") (name "Net-(R12-A)") (class "Default")
      (node (ref "R12") (pin "1") (pinfunction "A_1") (pintype "passive"))
      (node (ref "U4") (pin "26") (pinfunction "USB_DP_26") (pintype "passive"))
    )
    (net (code "45") (name "Net-(R12-Pad2)") (class "Default")
      (node (ref "R12") (pin "2") (pinfunction "2_2") (pintype "passive"))
      (node (ref "U6") (pin "4") (pinfunction "I/O2_4") (pintype "bidirectional"))
    )
    (net (code "46") (name "Net-(R13-Pad2)") (class "Default")
      (node (ref "R13") (pin "2") (pinfunction "2_2") (pintype "passive"))
      (node (ref "U7") (pin "6") (pinfunction "I/O1_6") (pintype "bidirectional"))
    )
    (net (code "47") (name "Net-(R14-Pad2)") (class "Default")
      (node (ref "R14") (pin "2") (pinfunction "2_2") (pintype "passive"))
      (node (ref "U7") (pin "4") (pinfunction "I/O2_4") (pintype "bidirectional"))
    )
    (net (code "48") (name "Net-(U1-COMP)") (class "Default")
      (node (ref "C2") (pin "2") (pinfunction "2_2") (pintype "passive"))
      (node (ref "U1") (pin "16") (pinfunction "COMP_16") (pintype "passive"))
    )
    (net (code "49") (name "Net-(U1-REFIN)") (class "Default")
      (node (ref "C1") (pin "1") (pinfunction "1_1") (pintype "passive"))
      (node (ref "U1") (pin "2") (pinfunction "REFIN_2") (pintype "input"))
      (node (ref "U1") (pin "3") (pinfunction "REFOUT_3") (pintype "output"))
    )
    (net (code "50") (name "Net-(U3-V(SENSE))") (class "Default")
      (node (ref "R6") (pin "2") (pinfunction "2_2") (pintype "passive"))
      (node (ref "U3") (pin "3") (pinfunction "V(SENSE)_3") (pintype "input"))
      (node (ref "U3") (pin "4") (pinfunction "VOUT_4") (pintype "tri_state"))
    )
    (net (code "51") (name "Net-(U4-VCC_RF)") (class "Default")
      (node (ref "R9") (pin "2") (pinfunction "2_2") (pintype "passive"))
      (node (ref "U4") (pin "18") (pinfunction "VCC_RF_18") (pintype "passive"))
    )
    (net (code "52") (name "Net-(U5E-TCK)") (class "Default")
      (node (ref "P4") (pin "4") (pinfunction "4_4") (pintype "passive"))
      (node (ref "U5") (pin "11") (pinfunction "TCK_11") (pintype "input"))
    )
    (net (code "53") (name "Net-(U5E-TDI)") (class "Default")
      (node (ref "P4") (pin "2") (pinfunction "2_2") (pintype "passive"))
      (node (ref "U5") (pin "9") (pinfunction "TDI_9") (pintype "input"))
    )
    (net (code "54") (name "Net-(U5E-TDO)") (class "Default")
      (node (ref "P4") (pin "3") (pinfunction "3_3") (pintype "passive"))
      (node (ref "U5") (pin "24") (pinfunction "TDO_24") (pintype "output"))
    )
    (net (code "55") (name "Net-(U5E-TMS)") (class "Default")
      (node (ref "P4") (pin "5") (pinfunction "5_5") (pintype "passive"))
      (node (ref "U5") (pin "10") (pinfunction "TMS_10") (pintype "input"))
    )
    (net (code "56") (name "Net-(U6-I{slash}O1-Pad1)") (class "Default")
      (node (ref "U6") (pin "1") (pinfunction "I/O1_1") (pintype "bidirectional"))
      (node (ref "USB_debug") (pin "2") (pinfunction "2_2") (pintype "passive"))
    )
    (net (code "57") (name "Net-(U6-I{slash}O2-Pad3)") (class "Default")
      (node (ref "U6") (pin "3") (pinfunction "I/O2_3") (pintype "bidirectional"))
      (node (ref "USB_debug") (pin "3") (pinfunction "3_3") (pintype "passive"))
    )
    (net (code "58") (name "Net-(U6-Vbus)") (class "Default")
      (node (ref "C27") (pin "2") (pinfunction "2_2") (pintype "passive"))
      (node (ref "U6") (pin "5") (pinfunction "Vbus_5") (pintype "power_in"))
      (node (ref "U8") (pin "3") (pinfunction "VIN_3") (pintype "power_in"))
      (node (ref "USB_debug") (pin "1") (pinfunction "1_1") (pintype "passive"))
    )
    (net (code "59") (name "unconnected-(D1-K2-Pad2)") (class "Default")
      (node (ref "D1") (pin "2") (pinfunction "K2_2") (pintype "passive"))
    )
    (net (code "60") (name "unconnected-(IC2-NC-Pad1)") (class "Default")
      (node (ref "IC2") (pin "1") (pinfunction "NC_1") (pintype "passive"))
    )
    (net (code "61") (name "unconnected-(P2-Pad1)") (class "Default")
      (node (ref "P2") (pin "1") (pinfunction "1_1") (pintype "passive"))
    )
    (net (code "62") (name "unconnected-(P2-Pad2)") (class "Default")
      (node (ref "P2") (pin "2") (pinfunction "2_2") (pintype "passive"))
    )
    (net (code "63") (name "unconnected-(P2-Pad3)") (class "Default")
      (node (ref "P2") (pin "3") (pinfunction "3_3") (pintype "passive"))
    )
    (net (code "64") (name "unconnected-(P2-Pad4)") (class "Default")
      (node (ref "P2") (pin "4") (pinfunction "4_4") (pintype "passive"))
    )
    (net (code "65") (name "unconnected-(P2-Pad5)") (class "Default")
      (node (ref "P2") (pin "5") (pinfunction "5_5") (pintype "passive"))
    )
    (net (code "66") (name "unconnected-(P2-Pad6)") (class "Default")
      (node (ref "P2") (pin "6") (pinfunction "6_6") (pintype "passive"))
    )
    (net (code "67") (name "unconnected-(P2-Pad7)") (class "Default")
      (node (ref "P2") (pin "7") (pinfunction "7_7") (pintype "passive"))
    )
    (net (code "68") (name "unconnected-(P2-Pad8)") (class "Default")
      (node (ref "P2") (pin "8") (pinfunction "8_8") (pintype "passive"))
    )
    (net (code "69") (name "unconnected-(P2-Pad9)") (class "Default")
      (node (ref "P2") (pin "9") (pinfunction "9_9") (pintype "passive"))
    )
    (net (code "70") (name "unconnected-(P2-Pad10)") (class "Default")
      (node (ref "P2") (pin "10") (pinfunction "10_10") (pintype "passive"))
    )
    (net (code "71") (name "unconnected-(P2-Pad11)") (class "Default")
      (node (ref "P2") (pin "11") (pinfunction "11_11") (pintype "passive"))
    )
    (net (code "72") (name "unconnected-(P2-Pad12)") (class "Default")
      (node (ref "P2") (pin "12") (pinfunction "12_12") (pintype "passive"))
    )
    (net (code "73") (name "unconnected-(P2-Pad13)") (class "Default")
      (node (ref "P2") (pin "13") (pinfunction "13_13") (pintype "passive"))
    )
    (net (code "74") (name "unconnected-(P2-Pad14)") (class "Default")
      (node (ref "P2") (pin "14") (pinfunction "14_14") (pintype "passive"))
    )
    (net (code "75") (name "unconnected-(P2-Pad15)") (class "Default")
      (node (ref "P2") (pin "15") (pinfunction "15_15") (pintype "passive"))
    )
    (net (code "76") (name "unconnected-(P2-Pad16)") (class "Default")
      (node (ref "P2") (pin "16") (pinfunction "16_16") (pintype "passive"))
    )
    (net (code "77") (name "unconnected-(P2-Pad17)") (class "Default")
      (node (ref "P2") (pin "17") (pinfunction "17_17") (pintype "passive"))
    )
    (net (code "78") (name "unconnected-(P2-Pad18)") (class "Default")
      (node (ref "P2") (pin "18") (pinfunction "18_18") (pintype "passive"))
    )
    (net (code "79") (name "unconnected-(P2-Pad19)") (class "Default")
      (node (ref "P2") (pin "19") (pinfunction "19_19") (pintype "passive"))
    )
    (net (code "80") (name "unconnected-(P2-Pad20)") (class "Default")
      (node (ref "P2") (pin "20") (pinfunction "20_20") (pintype "passive"))
    )
    (net (code "81") (name "unconnected-(P2-Pad21)") (class "Default")
      (node (ref "P2") (pin "21") (pinfunction "21_21") (pintype "passive"))
    )
    (net (code "82") (name "unconnected-(P2-Pad22)") (class "Default")
      (node (ref "P2") (pin "22") (pinfunction "22_22") (pintype "passive"))
    )
    (net (code "83") (name "unconnected-(P2-Pad23)") (class "Default")
      (node (ref "P2") (pin "23") (pinfunction "23_23") (pintype "passive"))
    )
    (net (code "84") (name "unconnected-(P2-Pad24)") (class "Default")
      (node (ref "P2") (pin "24") (pinfunction "24_24") (pintype "passive"))
    )
    (net (code "85") (name "unconnected-(P2-Pad25)") (class "Default")
      (node (ref "P2") (pin "25") (pinfunction "25_25") (pintype "passive"))
    )
    (net (code "86") (name "unconnected-(P2-Pad26)") (class "Default")
      (node (ref "P2") (pin "26") (pinfunction "26_26") (pintype "passive"))
    )
    (net (code "87") (name "unconnected-(P2-Pad27)") (class "Default")
      (node (ref "P2") (pin "27") (pinfunction "27_27") (pintype "passive"))
    )
    (net (code "88") (name "unconnected-(P2-Pad28)") (class "Default")
      (node (ref "P2") (pin "28") (pinfunction "28_28") (pintype "passive"))
    )
    (net (code "89") (name "unconnected-(P2-Pad29)") (class "Default")
      (node (ref "P2") (pin "29") (pinfunction "29_29") (pintype "passive"))
    )
    (net (code "90") (name "unconnected-(P2-Pad30)") (class "Default")
      (node (ref "P2") (pin "30") (pinfunction "30_30") (pintype "passive"))
    )
    (net (code "91") (name "unconnected-(P2-Pad31)") (class "Default")
      (node (ref "P2") (pin "31") (pinfunction "31_31") (pintype "passive"))
    )
    (net (code "92") (name "unconnected-(P2-Pad32)") (class "Default")
      (node (ref "P2") (pin "32") (pinfunction "32_32") (pintype "passive"))
    )
    (net (code "93") (name "unconnected-(P2-Pad33)") (class "Default")
      (node (ref "P2") (pin "33") (pinfunction "33_33") (pintype "passive"))
    )
    (net (code "94") (name "unconnected-(P2-Pad34)") (class "Default")
      (node (ref "P2") (pin "34") (pinfunction "34_34") (pintype "passive"))
    )
    (net (code "95") (name "unconnected-(P2-Pad35)") (class "Default")
      (node (ref "P2") (pin "35") (pinfunction "35_35") (pintype "passive"))
    )
    (net (code "96") (name "unconnected-(P2-Pad36)") (class "Default")
      (node (ref "P2") (pin "36") (pinfunction "36_36") (pintype "passive"))
    )
    (net (code "97") (name "unconnected-(U4-EXTIN1-Pad20)") (class "Default")
      (node (ref "U4") (pin "20") (pinfunction "EXTIN1_20") (pintype "passive"))
    )
    (net (code "98") (name "unconnected-(U4-RESERVED-Pad5)") (class "Default")
      (node (ref "U4") (pin "5") (pinfunction "RESERVED_5") (pintype "passive"))
    )
    (net (code "99") (name "unconnected-(U4-RESET_N-Pad10)") (class "Default")
      (node (ref "U4") (pin "10") (pinfunction "RESET_N_10") (pintype "passive"))
    )
    (net (code "100") (name "unconnected-(U4-SAFEBOOT_N-Pad12)") (class "Default")
      (node (ref "U4") (pin "12") (pinfunction "SAFEBOOT_N_12") (pintype "passive"))
    )
    (net (code "101") (name "unconnected-(U4-SCL-Pad2)") (class "Default")
      (node (ref "U4") (pin "2") (pinfunction "SCL_2") (pintype "passive"))
    )
    (net (code "102") (name "unconnected-(U4-SDA-Pad1)") (class "Default")
      (node (ref "U4") (pin "1") (pinfunction "SDA_1") (pintype "passive"))
    )
    (net (code "103") (name "unconnected-(U4-VCC_OUT-Pad8)") (class "Default")
      (node (ref "U4") (pin "8") (pinfunction "VCC_OUT_8") (pintype "passive"))
    )
    (net (code "104") (name "unconnected-(U5A-I{slash}O-Pad3)") (class "Default")
      (node (ref "U5") (pin "3") (pinfunction "I/O_3") (pintype "bidirectional"))
    )
    (net (code "105") (name "unconnected-(U5B-I{slash}O-Pad37)") (class "Default")
      (node (ref "U5") (pin "37") (pinfunction "I/O_37") (pintype "bidirectional"))
    )
    (net (code "106") (name "unconnected-(U5D-I{slash}O-Pad19)") (class "Default")
      (node (ref "U5") (pin "19") (pinfunction "I/O_19") (pintype "bidirectional"))
    )
    (net (code "107") (name "unconnected-(U5D-I{slash}O-Pad20)") (class "Default")
      (node (ref "U5") (pin "20") (pinfunction "I/O_20") (pintype "bidirectional"))
    )
    (net (code "108") (name "unconnected-(U5D-I{slash}O-Pad21)") (class "Default")
      (node (ref "U5") (pin "21") (pinfunction "I/O_21") (pintype "bidirectional"))
    )
    (net (code "109") (name "unconnected-(U5D-I{slash}O-Pad22)") (class "Default")
      (node (ref "U5") (pin "22") (pinfunction "I/O_22") (pintype "bidirectional"))
    )
    (net (code "110") (name "unconnected-(USB_debug-Pad4)") (class "Default")
      (node (ref "USB_debug") (pin "4") (pinfunction "4_4") (pintype "passive"))
    )
  )
)
